# J2_RefClkAndRTC.net
KiCad netlist of a schematic drawn in Altium Designer
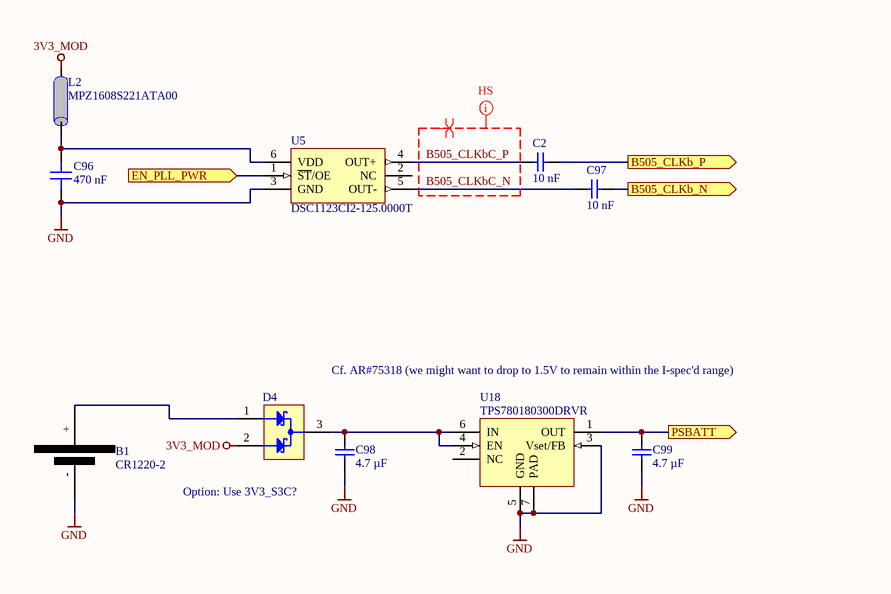
[diagram p0: J2_RefClkAndRTC.SchDoc]

(export (version "E")
  (design (tool "Eeschema 10.0.6"))
  (components
    (comp (ref "B1")
      (value "CR1220-2")
      (footprint "CR1220")
      (description "Battery base CR1220 SMD Button And Strip Battery Connector ROHS")
      (fields
        (field (name "MANUFACTURER") "Q&J")
        (field (name "LCSC PART NUMBER") "C70381")
        (field (name "CREATED FROM") "FRosner")
      )
      (libsource (lib "user") (part "CR1220"))
    )
    (comp (ref "C2")
      (value "10 nF")
      (footprint "C_0402_TE")
      (description "Generic capacitor")
      (fields
        (field (name "VOLTAGE") "16V")
        (field (name "TOLERANCE") "10 %")
        (field (name "CREATED FROM") "UZgenTool")
      )
      (libsource (lib "user") (part "CAP-NP"))
    )
    (comp (ref "C96")
      (value "470 nF")
      (footprint "C_0603_TE")
      (description "Capacitor 0603, 50 VDC, 470 nF, X5R")
      (fields
        (field (name "MANUFACTURER PART NUMBER") "CL10A474KB8NNNC")
        (field (name "MANUFACTURER") "Samsung Electro-Mechanics")
        (field (name "CREATED FROM") "AGeiger")
      )
      (libsource (lib "user") (part "Capacitor"))
    )
    (comp (ref "C97")
      (value "10 nF")
      (footprint "C_0402_TE")
      (description "Generic capacitor")
      (fields
        (field (name "VOLTAGE") "16V")
        (field (name "TOLERANCE") "10 %")
        (field (name "CREATED FROM") "UZgenTool")
      )
      (libsource (lib "user") (part "CAP-NP"))
    )
    (comp (ref "C98")
      (value "4.7 µF")
      (footprint "C_0603_TE")
      (description "Generic capacitor")
      (fields
        (field (name "MANUFACTURER PART NUMBER") "UZgen_C_0603_4.7uF_16V_X5R")
        (field (name "MANUFACTURER") "UZgen")
        (field (name "CREATED FROM") "MGeier")
      )
      (libsource (lib "user") (part "CAP-NP"))
    )
    (comp (ref "C99")
      (value "4.7 µF")
      (footprint "C_0603_TE")
      (description "Generic capacitor")
      (fields
        (field (name "MANUFACTURER PART NUMBER") "UZgen_C_0603_4.7uF_16V_X5R")
        (field (name "MANUFACTURER") "UZgen")
        (field (name "CREATED FROM") "MGeier")
      )
      (libsource (lib "user") (part "CAP-NP"))
    )
    (comp (ref "D4")
      (value "BAT54CT-7-F")
      (footprint "SOT523-3")
      (description "Surface-mount Schottky Barrier Diode, 1 Pair Common Cathode 1V@100mA 200mA 2uA@25V 30V SOT-523-3")
      (fields
        (field (name "MANUFACTURER") "Diodes Incorporated")
        (field (name "LCSC PART NUMBER") "C134407")
        (field (name "CREATED FROM") "MGeier")
      )
      (libsource (lib "user") (part "DualCommonCathode3K"))
    )
    (comp (ref "L2")
      (value "MPZ1608S221ATA00")
      (footprint "RES 0603_1608")
      (description "Ferritperle, 0603, 220 ohm, 2.2 A, Baureihe MPZ, 0.05 ohm, ± 25%")
      (fields
        (field (name "MANUFACTURER") "TDK")
        (field (name "LCSC PART NUMBER") "C76815")
        (field (name "CREATED FROM") "MGremer")
      )
      (libsource (lib "user") (part "Ferrite_Bead"))
    )
    (comp (ref "U5")
      (value "DSC1123CI2-125.0000T")
      (footprint "PSON105P320X250X90-6N")
      (description "Standard Clock Oscillators MEMS OSC, LVDS, 125MHz, 25PPM, 2.5-3.3V, -40 to 85C, 3.2 x 2.5mm")
      (fields
        (field (name "MANUFACTURER") "Microchip")
        (field (name "LCSC PART NUMBER") "C1987227")
        (field (name "CREATED FROM") "FRosner")
      )
      (libsource (lib "user") (part "DSC1123CI2"))
    )
    (comp (ref "U18")
      (value "TPS780180300DRVR")
      (footprint "SON65P200X200X80-7N")
      (description "LDO Voltage Regulators 150mA,LDO Reg,Ultra Low Pwr")
      (fields
        (field (name "MANUFACTURER") "Texas Instruments")
        (field (name "LCSC PART NUMBER") "C2860011")
        (field (name "CREATED FROM") "FRosner")
      )
      (libsource (lib "user") (part "TPS780180300DRV"))
    )
  )
  (nets
    (net (code "1") (name "/B505_CLKbC_N") (class "Default")
      (node (ref "C97") (pin "1") (pinfunction "1_1") (pintype "passive"))
      (node (ref "U5") (pin "5") (pinfunction "OUT-_5") (pintype "output"))
    )
    (net (code "2") (name "/B505_CLKbC_P") (class "Default")
      (node (ref "C2") (pin "1") (pinfunction "1_1") (pintype "passive"))
      (node (ref "U5") (pin "4") (pinfunction "OUT+_4") (pintype "output"))
    )
    (net (code "3") (name "/B505_CLKb_N") (class "Default")
      (node (ref "C97") (pin "2") (pinfunction "2_2") (pintype "passive"))
    )
    (net (code "4") (name "/B505_CLKb_P") (class "Default")
      (node (ref "C2") (pin "2") (pinfunction "2_2") (pintype "passive"))
    )
    (net (code "5") (name "/EN_PLL_PWR") (class "Default")
      (node (ref "U5") (pin "1") (pinfunction "~{ST}/OE_1") (pintype "input"))
    )
    (net (code "6") (name "/PSBATT") (class "Default")
      (node (ref "C99") (pin "2") (pinfunction "2_2") (pintype "passive"))
      (node (ref "U18") (pin "1") (pinfunction "OUT_1") (pintype "passive"))
    )
    (net (code "7") (name "3V3_MOD") (class "Default")
      (node (ref "D4") (pin "2") (pinfunction "A_2") (pintype "passive"))
      (node (ref "L2") (pin "1") (pinfunction "1_1") (pintype "passive"))
    )
    (net (code "8") (name "GND") (class "Default")
      (node (ref "B1") (pin "-") (pinfunction "-_-") (pintype "power_in"))
      (node (ref "C96") (pin "1") (pinfunction "1_1") (pintype "passive"))
      (node (ref "C98") (pin "1") (pinfunction "1_1") (pintype "passive"))
      (node (ref "C99") (pin "1") (pinfunction "1_1") (pintype "passive"))
      (node (ref "U18") (pin "3") (pinfunction "Vset/FB_3") (pintype "input"))
      (node (ref "U18") (pin "5") (pinfunction "GND_5") (pintype "power_in"))
      (node (ref "U18") (pin "7") (pinfunction "PAD_7") (pintype "passive"))
      (node (ref "U5") (pin "3") (pinfunction "GND_3") (pintype "power_in"))
    )
    (net (code "9") (name "Net-(B1-Pad+)") (class "Default")
      (node (ref "B1") (pin "+") (pinfunction "+_+") (pintype "power_in"))
      (node (ref "D4") (pin "1") (pinfunction "A_1") (pintype "passive"))
    )
    (net (code "10") (name "Net-(D4-K)") (class "Default")
      (node (ref "C98") (pin "2") (pinfunction "2_2") (pintype "passive"))
      (node (ref "D4") (pin "3") (pinfunction "K_3") (pintype "passive"))
      (node (ref "U18") (pin "4") (pinfunction "EN_4") (pintype "input"))
      (node (ref "U18") (pin "6") (pinfunction "IN_6") (pintype "power_in"))
    )
    (net (code "11") (name "Net-(U5-VDD)") (class "Default")
      (node (ref "C96") (pin "2") (pinfunction "2_2") (pintype "passive"))
      (node (ref "L2") (pin "2") (pinfunction "2_2") (pintype "passive"))
      (node (ref "U5") (pin "6") (pinfunction "VDD_6") (pintype "power_in"))
    )
    (net (code "12") (name "unconnected-(U5-NC-Pad2)") (class "Default")
      (node (ref "U5") (pin "2") (pinfunction "NC_2") (pintype "passive"))
    )
    (net (code "13") (name "unconnected-(U18-NC-Pad2)") (class "Default")
      (node (ref "U18") (pin "2") (pinfunction "NC_2") (pintype "passive"))
    )
  )
)
